# Frequency_Control.net
KiCad netlist of a schematic drawn in EAGLE
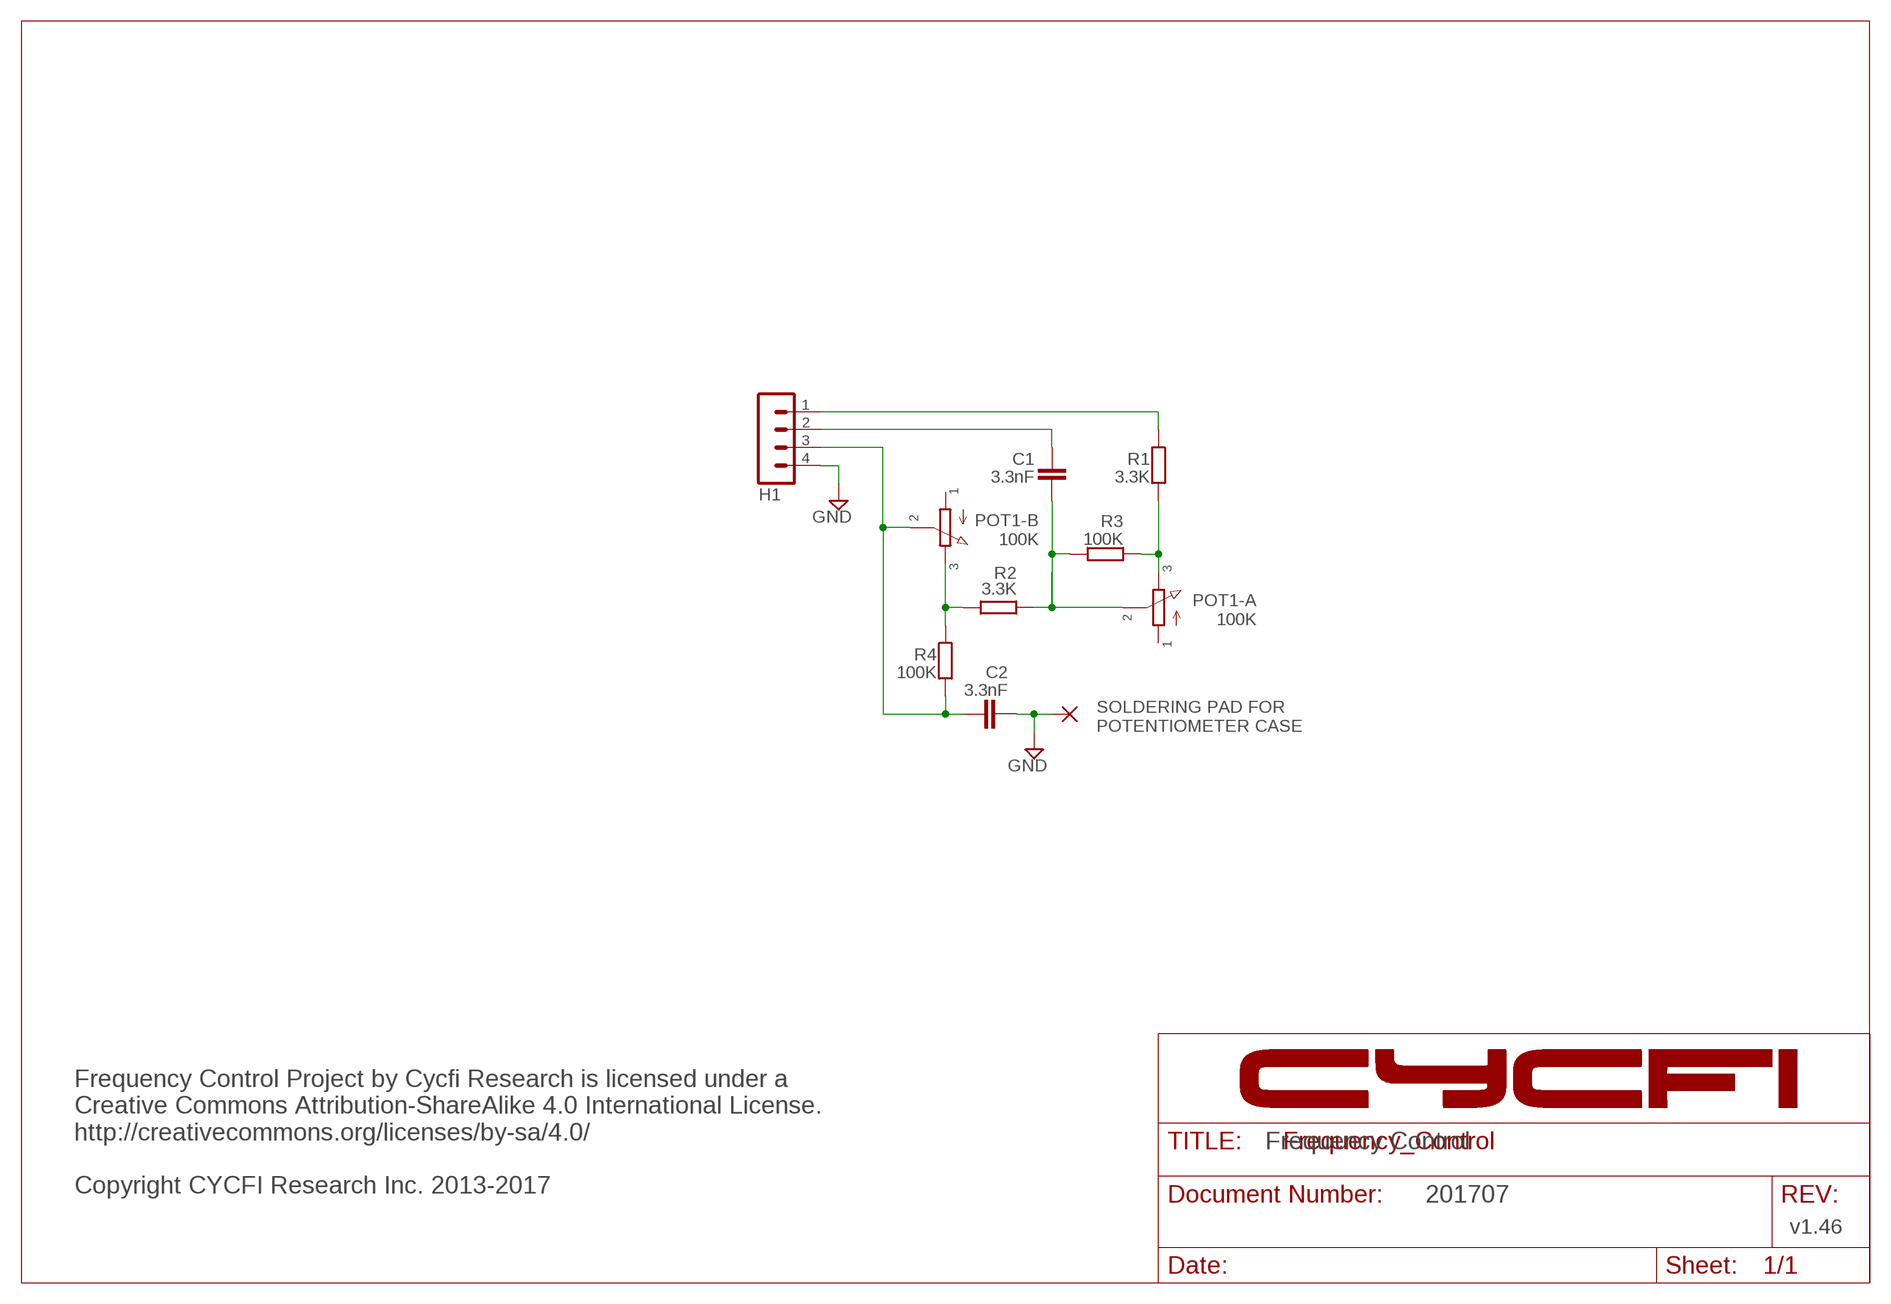
[diagram p0: schematic, sheet 1]

(export (version "E")
  (design (tool "Eeschema 10.0.6"))
  (components
    (comp (ref "C1")
      (value "3.3nF")
      (footprint "eagle-import:C0805")
      (libsource (lib "eagle-import") (part "C-EUC0805"))
    )
    (comp (ref "C2")
      (value "3.3nF")
      (footprint "eagle-import:C0805")
      (libsource (lib "eagle-import") (part "C-EUC0805"))
    )
    (comp (ref "H1")
      (value "MA04-1")
      (footprint "eagle-import:MA04-1")
      (libsource (lib "eagle-import") (part "MA04-1"))
    )
    (comp (ref "PAD1")
      (value "1,6/0,9")
      (footprint "eagle-import:1,6_0,9")
      (libsource (lib "eagle-import") (part "1,6/0,9"))
    )
    (comp (ref "POT1-A")
      (value "PDB182-GTR02")
      (footprint "eagle-import:PDB182-GTR01")
      (libsource (lib "eagle-import") (part "PDB182-GTR02"))
    )
    (comp (ref "R1")
      (value "3.3K")
      (footprint "eagle-import:R0603")
      (libsource (lib "eagle-import") (part "R-EU_R0603"))
    )
    (comp (ref "R2")
      (value "3.3K")
      (footprint "eagle-import:R0603")
      (libsource (lib "eagle-import") (part "R-EU_R0603"))
    )
    (comp (ref "R3")
      (value "100K")
      (footprint "eagle-import:R0402")
      (libsource (lib "eagle-import") (part "R-EU_R0402"))
    )
    (comp (ref "R4")
      (value "100K")
      (footprint "eagle-import:R0402")
      (libsource (lib "eagle-import") (part "R-EU_R0402"))
    )
  )
  (nets
    (net (code "1") (name "GND") (class "Default")
      (node (ref "C2") (pin "2") (pinfunction "2_2") (pintype "passive"))
      (node (ref "H1") (pin "4") (pinfunction "4_4") (pintype "passive"))
      (node (ref "PAD1") (pin "1") (pinfunction "P_1") (pintype "passive"))
    )
    (net (code "2") (name "Net-(C1-Pad2)") (class "Default")
      (node (ref "C1") (pin "2") (pinfunction "2_2") (pintype "passive"))
      (node (ref "H1") (pin "2") (pinfunction "2_2") (pintype "passive"))
    )
    (net (code "3") (name "Net-(H1-Pad1)") (class "Default")
      (node (ref "H1") (pin "1") (pinfunction "1_1") (pintype "passive"))
      (node (ref "R1") (pin "1") (pinfunction "1_1") (pintype "passive"))
    )
    (net (code "4") (name "Net-(POT1-AA-2)") (class "Default")
      (node (ref "C1") (pin "1") (pinfunction "1_1") (pintype "passive"))
      (node (ref "POT1-A") (pin "A2") (pinfunction "2_A2") (pintype "passive"))
      (node (ref "R2") (pin "1") (pinfunction "1_1") (pintype "passive"))
      (node (ref "R3") (pin "1") (pinfunction "1_1") (pintype "passive"))
    )
    (net (code "5") (name "Net-(POT1-AA-3)") (class "Default")
      (node (ref "POT1-A") (pin "A3") (pinfunction "3_A3") (pintype "passive"))
      (node (ref "R1") (pin "2") (pinfunction "2_2") (pintype "passive"))
      (node (ref "R3") (pin "2") (pinfunction "2_2") (pintype "passive"))
    )
    (net (code "6") (name "Net-(POT1-AB-2)") (class "Default")
      (node (ref "C2") (pin "1") (pinfunction "1_1") (pintype "passive"))
      (node (ref "H1") (pin "3") (pinfunction "3_3") (pintype "passive"))
      (node (ref "POT1-A") (pin "B2") (pinfunction "2_B2") (pintype "passive"))
      (node (ref "R4") (pin "2") (pinfunction "2_2") (pintype "passive"))
    )
    (net (code "7") (name "Net-(POT1-AB-3)") (class "Default")
      (node (ref "POT1-A") (pin "B3") (pinfunction "3_B3") (pintype "passive"))
      (node (ref "R2") (pin "2") (pinfunction "2_2") (pintype "passive"))
      (node (ref "R4") (pin "1") (pinfunction "1_1") (pintype "passive"))
    )
    (net (code "8") (name "unconnected-(POT1-AA-1-PadA1)") (class "Default")
      (node (ref "POT1-A") (pin "A1") (pinfunction "1_A1") (pintype "passive"))
    )
    (net (code "9") (name "unconnected-(POT1-AB-1-PadB1)") (class "Default")
      (node (ref "POT1-A") (pin "B1") (pinfunction "1_B1") (pintype "passive"))
    )
  )
)
